# 4_-_Latching.net
KiCad netlist of a schematic drawn in Altium Designer
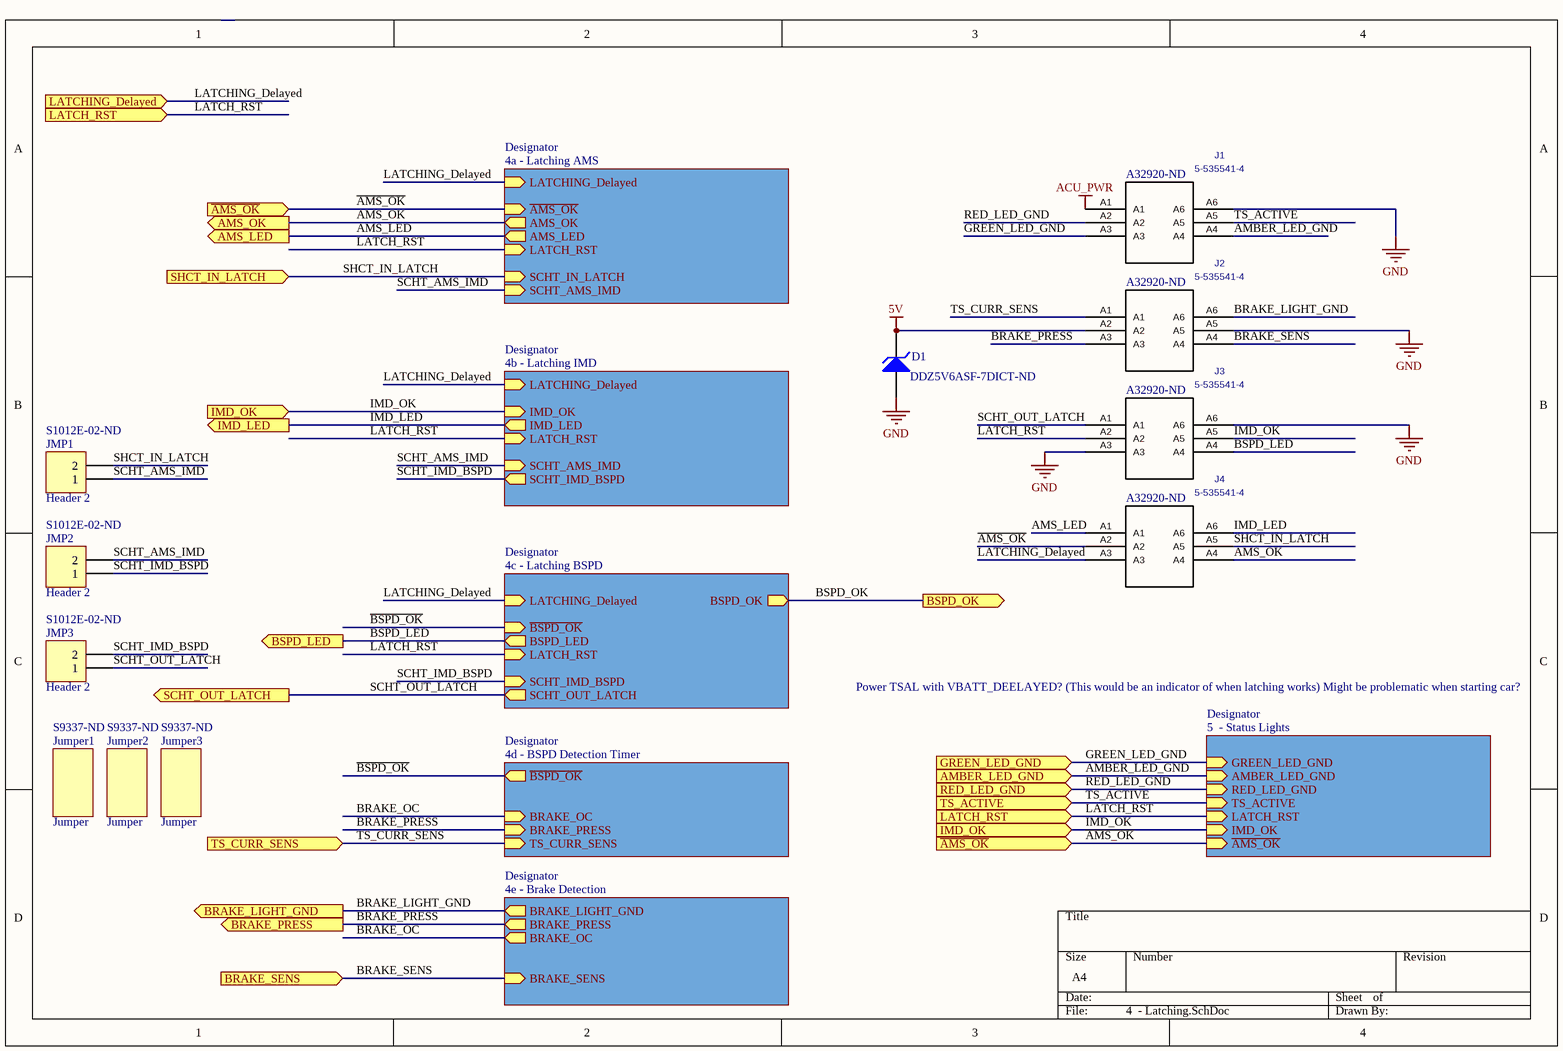
[diagram p0: 4  - Latching.SchDoc]

(export (version "E")
  (design (tool "Eeschema 10.0.6"))
  (components
    (comp (ref "D1")
      (value "D Zener")
      (footprint "DIODE_SOD323_101")
      (description "Zener Diode")
      (fields
        (field (name "SUPPLIER PART NUMBER 1") "DDZ5V6ASF-7DICT-ND")
        (field (name "PUBLISHER") "Altium Limited")
      )
      (libsource (lib "Miscellaneous Devices") (part "D Zener"))
    )
    (comp (ref "J1")
      (value "5-535541-4")
      (footprint "5-535541-4_5-535541-4(Primary)")
      (fields (field (name "SUPPLIER PART NUMBER 1") "A32920-ND"))
      (libsource (lib "ACB_lib") (part "5-535541-4"))
    )
    (comp (ref "J2")
      (value "5-535541-4")
      (footprint "5-535541-4_5-535541-4(Primary)")
      (fields (field (name "SUPPLIER PART NUMBER 1") "A32920-ND"))
      (libsource (lib "ACB_lib") (part "5-535541-4"))
    )
    (comp (ref "J3")
      (value "5-535541-4")
      (footprint "5-535541-4_5-535541-4(Primary)")
      (fields (field (name "SUPPLIER PART NUMBER 1") "A32920-ND"))
      (libsource (lib "ACB_lib") (part "5-535541-4"))
    )
    (comp (ref "J4")
      (value "5-535541-4")
      (footprint "5-535541-4_5-535541-4(Primary)")
      (fields (field (name "SUPPLIER PART NUMBER 1") "A32920-ND"))
      (libsource (lib "ACB_lib") (part "5-535541-4"))
    )
    (comp (ref "JMP1")
      (value "Header 2")
      (footprint "2Pin Jumper")
      (description "Header, 2-Pin")
      (fields
        (field (name "MANUFACTURER") "Harwin Inc.")
        (field (name "MANUFACTURER PART NUMBER") "M20-9990246")
        (field (name "SUPPLIER PART NUMBER 1") "S1012E-02-ND")
        (field (name "PUBLISHER") "Altium Limited")
      )
      (libsource (lib "Miscellaneous Connectors") (part "Header 2"))
    )
    (comp (ref "JMP2")
      (value "Header 2")
      (footprint "2Pin Jumper")
      (description "Header, 2-Pin")
      (fields
        (field (name "MANUFACTURER") "Harwin Inc.")
        (field (name "MANUFACTURER PART NUMBER") "M20-9990246")
        (field (name "SUPPLIER PART NUMBER 1") "S1012E-02-ND")
        (field (name "PUBLISHER") "Altium Limited")
      )
      (libsource (lib "Miscellaneous Connectors") (part "Header 2"))
    )
    (comp (ref "JMP3")
      (value "Header 2")
      (footprint "2Pin Jumper")
      (description "Header, 2-Pin")
      (fields
        (field (name "MANUFACTURER") "Harwin Inc.")
        (field (name "MANUFACTURER PART NUMBER") "M20-9990246")
        (field (name "SUPPLIER PART NUMBER 1") "S1012E-02-ND")
        (field (name "PUBLISHER") "Altium Limited")
      )
      (libsource (lib "Miscellaneous Connectors") (part "Header 2"))
    )
    (comp (ref "Jumper1")
      (value "Jumper")
      (fields (field (name "SUPPLIER PART NUMBER 1") "S9337-ND"))
      (libsource (lib "BRAKE TEMP Components") (part "Jumper"))
    )
    (comp (ref "Jumper2")
      (value "Jumper")
      (fields (field (name "SUPPLIER PART NUMBER 1") "S9337-ND"))
      (libsource (lib "BRAKE TEMP Components") (part "Jumper"))
    )
    (comp (ref "Jumper3")
      (value "Jumper")
      (fields (field (name "SUPPLIER PART NUMBER 1") "S9337-ND"))
      (libsource (lib "BRAKE TEMP Components") (part "Jumper"))
    )
  )
  (nets
    (net (code "1") (name "/AMBER_LED_GND") (class "Default")
      (node (ref "J1") (pin "A4") (pinfunction "A4_A4") (pintype "passive"))
    )
    (net (code "2") (name "/AMS_LED") (class "Default")
      (node (ref "J4") (pin "A1") (pinfunction "A1_A1") (pintype "passive"))
    )
    (net (code "3") (name "/AMS_OK") (class "Default")
      (node (ref "J4") (pin "A4") (pinfunction "A4_A4") (pintype "passive"))
    )
    (net (code "4") (name "/BRAKE_LIGHT_GND") (class "Default")
      (node (ref "J2") (pin "A6") (pinfunction "A6_A6") (pintype "passive"))
    )
    (net (code "6") (name "/BRAKE_PRESS") (class "Default")
      (node (ref "J2") (pin "A3") (pinfunction "A3_A3") (pintype "passive"))
    )
    (net (code "7") (name "/BRAKE_SENS") (class "Default")
      (node (ref "J2") (pin "A4") (pinfunction "A4_A4") (pintype "passive"))
    )
    (net (code "8") (name "/BSPD_LED") (class "Default")
      (node (ref "J3") (pin "A4") (pinfunction "A4_A4") (pintype "passive"))
    )
    (net (code "10") (name "/GREEN_LED_GND") (class "Default")
      (node (ref "J1") (pin "A3") (pinfunction "A3_A3") (pintype "passive"))
    )
    (net (code "11") (name "/IMD_LED") (class "Default")
      (node (ref "J4") (pin "A6") (pinfunction "A6_A6") (pintype "passive"))
    )
    (net (code "12") (name "/IMD_OK") (class "Default")
      (node (ref "J3") (pin "A5") (pinfunction "A5_A5") (pintype "passive"))
    )
    (net (code "13") (name "/LATCHING_Delayed") (class "Default")
      (node (ref "J4") (pin "A3") (pinfunction "A3_A3") (pintype "passive"))
    )
    (net (code "14") (name "/LATCH_RST") (class "Default")
      (node (ref "J3") (pin "A2") (pinfunction "A2_A2") (pintype "passive"))
    )
    (net (code "15") (name "/RED_LED_GND") (class "Default")
      (node (ref "J1") (pin "A2") (pinfunction "A2_A2") (pintype "passive"))
    )
    (net (code "16") (name "/SCHT_AMS_IMD") (class "Default")
      (node (ref "JMP1") (pin "1") (pinfunction "1_1") (pintype "passive"))
      (node (ref "JMP2") (pin "2") (pinfunction "2_2") (pintype "passive"))
    )
    (net (code "17") (name "/SCHT_IMD_BSPD") (class "Default")
      (node (ref "JMP2") (pin "1") (pinfunction "1_1") (pintype "passive"))
      (node (ref "JMP3") (pin "2") (pinfunction "2_2") (pintype "passive"))
    )
    (net (code "18") (name "/SCHT_OUT_LATCH") (class "Default")
      (node (ref "J3") (pin "A1") (pinfunction "A1_A1") (pintype "passive"))
      (node (ref "JMP3") (pin "1") (pinfunction "1_1") (pintype "passive"))
    )
    (net (code "19") (name "/SHCT_IN_LATCH") (class "Default")
      (node (ref "J4") (pin "A5") (pinfunction "A5_A5") (pintype "passive"))
      (node (ref "JMP1") (pin "2") (pinfunction "2_2") (pintype "passive"))
    )
    (net (code "20") (name "/TS_ACTIVE") (class "Default")
      (node (ref "J1") (pin "A5") (pinfunction "A5_A5") (pintype "passive"))
    )
    (net (code "21") (name "/TS_CURR_SENS") (class "Default")
      (node (ref "J2") (pin "A1") (pinfunction "A1_A1") (pintype "passive"))
    )
    (net (code "22") (name "/~{AMS_OK}") (class "Default")
      (node (ref "J4") (pin "A2") (pinfunction "A2_A2") (pintype "passive"))
    )
    (net (code "24") (name "5V") (class "Default")
      (node (ref "D1") (pin "2") (pinfunction "K_2") (pintype "passive"))
      (node (ref "J2") (pin "A2") (pinfunction "A2_A2") (pintype "passive"))
    )
    (net (code "25") (name "ACU_PWR") (class "Default")
      (node (ref "J1") (pin "A1") (pinfunction "A1_A1") (pintype "passive"))
    )
    (net (code "26") (name "GND") (class "Default")
      (node (ref "D1") (pin "1") (pinfunction "A_1") (pintype "passive"))
      (node (ref "J1") (pin "A6") (pinfunction "A6_A6") (pintype "passive"))
      (node (ref "J2") (pin "A5") (pinfunction "A5_A5") (pintype "passive"))
      (node (ref "J3") (pin "A3") (pinfunction "A3_A3") (pintype "passive"))
      (node (ref "J3") (pin "A6") (pinfunction "A6_A6") (pintype "passive"))
    )
  )
)
